# Ethernet1_MDIO.net
KiCad netlist of a schematic drawn in Altium Designer
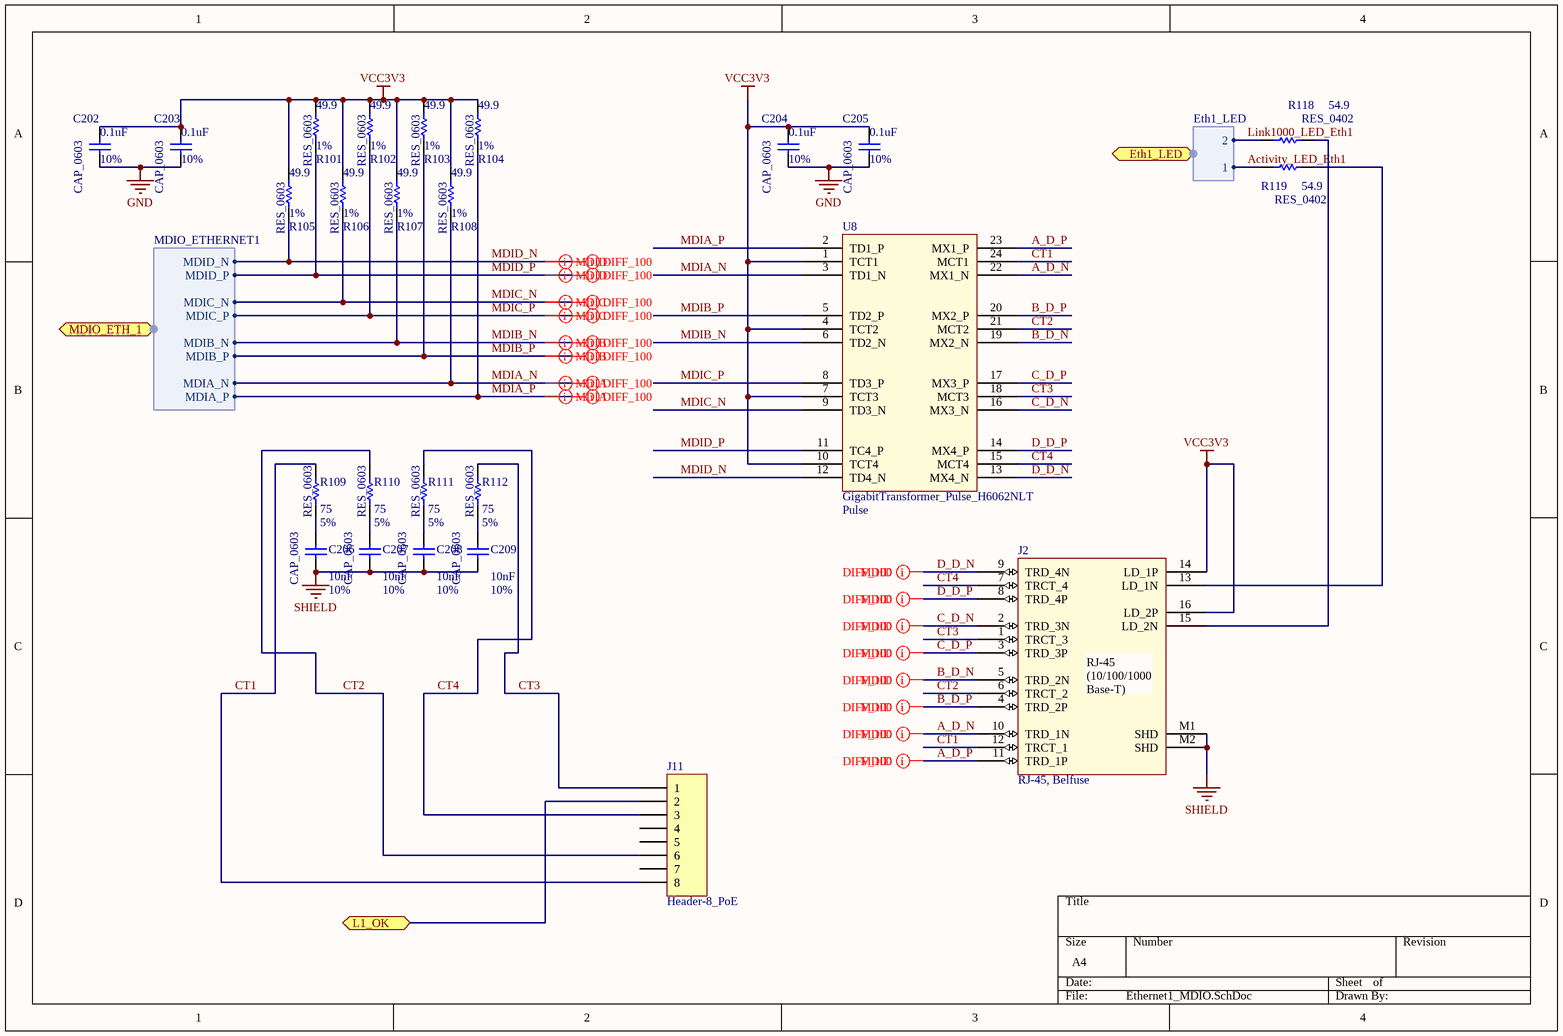
[diagram p0: Ethernet1_MDIO.SchDoc]

(export (version "E")
  (design (tool "Eeschema 10.0.6"))
  (components
    (comp (ref "C202")
      (value "CAP_0603")
      (footprint "CAPC0603(1608)100_N:CAPC0603(1608)100_N")
      (description "CAP CER 0.1UF 50V 10% X7R 0603")
      (fields
        (field (name "ALTIUM_VALUE") "0.1uF")
        (field (name "TOLERANCE") "10%")
        (field (name "PART NUMBER") "C0603C104K5RACTU")
        (field (name "MANUFACTURER") "Kemet")
      )
      (libsource (lib "COMRAD_Database") (part "CAP_0603"))
    )
    (comp (ref "C203")
      (value "CAP_0603")
      (footprint "CAPC0603(1608)100_N:CAPC0603(1608)100_N")
      (description "CAP CER 0.1UF 50V 10% X7R 0603")
      (fields
        (field (name "ALTIUM_VALUE") "0.1uF")
        (field (name "TOLERANCE") "10%")
        (field (name "PART NUMBER") "C0603C104K5RACTU")
        (field (name "MANUFACTURER") "Kemet")
      )
      (libsource (lib "COMRAD_Database") (part "CAP_0603"))
    )
    (comp (ref "C204")
      (value "CAP_0603")
      (footprint "CAPC0603(1608)100_N:CAPC0603(1608)100_N")
      (description "CAP CER 0.1UF 50V 10% X7R 0603")
      (fields
        (field (name "ALTIUM_VALUE") "0.1uF")
        (field (name "TOLERANCE") "10%")
        (field (name "PART NUMBER") "C0603C104K5RACTU")
        (field (name "MANUFACTURER") "Kemet")
      )
      (libsource (lib "COMRAD_Database") (part "CAP_0603"))
    )
    (comp (ref "C205")
      (value "CAP_0603")
      (footprint "CAPC0603(1608)100_N:CAPC0603(1608)100_N")
      (description "CAP CER 0.1UF 50V 10% X7R 0603")
      (fields
        (field (name "ALTIUM_VALUE") "0.1uF")
        (field (name "TOLERANCE") "10%")
        (field (name "PART NUMBER") "C0603C104K5RACTU")
        (field (name "MANUFACTURER") "Kemet")
      )
      (libsource (lib "COMRAD_Database") (part "CAP_0603"))
    )
    (comp (ref "C206")
      (value "CAP_0603")
      (footprint "CAPC0603(1608)100_N:CAPC0603(1608)100_N")
      (description "CAP CER 10000PF 50V 10% X7R 0603")
      (fields
        (field (name "ALTIUM_VALUE") "10nF")
        (field (name "TOLERANCE") "10%")
        (field (name "PART NUMBER") "C0603C103K5RACTU")
        (field (name "MANUFACTURER") "Kemet")
      )
      (libsource (lib "COMRAD_Database") (part "CAP_0603"))
    )
    (comp (ref "C207")
      (value "CAP_0603")
      (footprint "CAPC0603(1608)100_N:CAPC0603(1608)100_N")
      (description "CAP CER 10000PF 50V 10% X7R 0603")
      (fields
        (field (name "ALTIUM_VALUE") "10nF")
        (field (name "TOLERANCE") "10%")
        (field (name "PART NUMBER") "C0603C103K5RACTU")
        (field (name "MANUFACTURER") "Kemet")
      )
      (libsource (lib "COMRAD_Database") (part "CAP_0603"))
    )
    (comp (ref "C208")
      (value "CAP_0603")
      (footprint "CAPC0603(1608)100_N:CAPC0603(1608)100_N")
      (description "CAP CER 10000PF 50V 10% X7R 0603")
      (fields
        (field (name "ALTIUM_VALUE") "10nF")
        (field (name "TOLERANCE") "10%")
        (field (name "PART NUMBER") "C0603C103K5RACTU")
        (field (name "MANUFACTURER") "Kemet")
      )
      (libsource (lib "COMRAD_Database") (part "CAP_0603"))
    )
    (comp (ref "C209")
      (value "CAP_0603")
      (footprint "CAPC0603(1608)100_N:CAPC0603(1608)100_N")
      (description "CAP CER 10000PF 50V 10% X7R 0603")
      (fields
        (field (name "ALTIUM_VALUE") "10nF")
        (field (name "TOLERANCE") "10%")
        (field (name "PART NUMBER") "C0603C103K5RACTU")
        (field (name "MANUFACTURER") "Kemet")
      )
      (libsource (lib "COMRAD_Database") (part "CAP_0603"))
    )
    (comp (ref "J2")
      (value "RJ-45, Belfuse")
      (footprint "RJ-45_BelFuse_L834-1G1T-S7_pcb")
      (description "RJ-45, Belfuse, Gigabit Magnetic Jack")
      (fields (field (name "PART NUMBER") "L834-1G1T-S7") (field (name "MANUFACTURER") "Belfuse"))
      (libsource (lib "COMRAD_Database") (part "RJ-45_BelFuse_L8341GITS7"))
    )
    (comp (ref "J11")
      (value "Header-8_PoE")
      (footprint "Header_FCI_20021221-00008T4LF_8-pos")
      (description "CONN HEADER 8POS DUAL SHRD SMD")
      (fields (field (name "PART NUMBER") "20021221-00008T4LF") (field (name "MANUFACTURER") "FCI"))
      (libsource (lib "COMRAD_Database") (part "Header-8_PoE"))
    )
    (comp (ref "R101")
      (value "RES_0603")
      (footprint "RESC0603(1608)_N")
      (description "RES 49.9 OHM 1/10W 1% 0603 SMD")
      (fields
        (field (name "ALTIUM_VALUE") "49.9")
        (field (name "TOLERANCE") "1%")
        (field (name "PART NUMBER") "ERJ-3EKF49R9V")
        (field (name "MANUFACTURER") "Panasonic Electronics Components")
      )
      (libsource (lib "COMRAD_Database") (part "RES_0603"))
    )
    (comp (ref "R102")
      (value "RES_0603")
      (footprint "RESC0603(1608)_N")
      (description "RES 49.9 OHM 1/10W 1% 0603 SMD")
      (fields
        (field (name "ALTIUM_VALUE") "49.9")
        (field (name "TOLERANCE") "1%")
        (field (name "PART NUMBER") "ERJ-3EKF49R9V")
        (field (name "MANUFACTURER") "Panasonic Electronics Components")
      )
      (libsource (lib "COMRAD_Database") (part "RES_0603"))
    )
    (comp (ref "R103")
      (value "RES_0603")
      (footprint "RESC0603(1608)_N")
      (description "RES 49.9 OHM 1/10W 1% 0603 SMD")
      (fields
        (field (name "ALTIUM_VALUE") "49.9")
        (field (name "TOLERANCE") "1%")
        (field (name "PART NUMBER") "ERJ-3EKF49R9V")
        (field (name "MANUFACTURER") "Panasonic Electronics Components")
      )
      (libsource (lib "COMRAD_Database") (part "RES_0603"))
    )
    (comp (ref "R104")
      (value "RES_0603")
      (footprint "RESC0603(1608)_N")
      (description "RES 49.9 OHM 1/10W 1% 0603 SMD")
      (fields
        (field (name "ALTIUM_VALUE") "49.9")
        (field (name "TOLERANCE") "1%")
        (field (name "PART NUMBER") "ERJ-3EKF49R9V")
        (field (name "MANUFACTURER") "Panasonic Electronics Components")
      )
      (libsource (lib "COMRAD_Database") (part "RES_0603"))
    )
    (comp (ref "R105")
      (value "RES_0603")
      (footprint "RESC0603(1608)_N")
      (description "RES 49.9 OHM 1/10W 1% 0603 SMD")
      (fields
        (field (name "ALTIUM_VALUE") "49.9")
        (field (name "TOLERANCE") "1%")
        (field (name "PART NUMBER") "ERJ-3EKF49R9V")
        (field (name "MANUFACTURER") "Panasonic Electronics Components")
      )
      (libsource (lib "COMRAD_Database") (part "RES_0603"))
    )
    (comp (ref "R106")
      (value "RES_0603")
      (footprint "RESC0603(1608)_N")
      (description "RES 49.9 OHM 1/10W 1% 0603 SMD")
      (fields
        (field (name "ALTIUM_VALUE") "49.9")
        (field (name "TOLERANCE") "1%")
        (field (name "PART NUMBER") "ERJ-3EKF49R9V")
        (field (name "MANUFACTURER") "Panasonic Electronics Components")
      )
      (libsource (lib "COMRAD_Database") (part "RES_0603"))
    )
    (comp (ref "R107")
      (value "RES_0603")
      (footprint "RESC0603(1608)_N")
      (description "RES 49.9 OHM 1/10W 1% 0603 SMD")
      (fields
        (field (name "ALTIUM_VALUE") "49.9")
        (field (name "TOLERANCE") "1%")
        (field (name "PART NUMBER") "ERJ-3EKF49R9V")
        (field (name "MANUFACTURER") "Panasonic Electronics Components")
      )
      (libsource (lib "COMRAD_Database") (part "RES_0603"))
    )
    (comp (ref "R108")
      (value "RES_0603")
      (footprint "RESC0603(1608)_N")
      (description "RES 49.9 OHM 1/10W 1% 0603 SMD")
      (fields
        (field (name "ALTIUM_VALUE") "49.9")
        (field (name "TOLERANCE") "1%")
        (field (name "PART NUMBER") "ERJ-3EKF49R9V")
        (field (name "MANUFACTURER") "Panasonic Electronics Components")
      )
      (libsource (lib "COMRAD_Database") (part "RES_0603"))
    )
    (comp (ref "R109")
      (value "RES_0603")
      (footprint "RESC0603(1608)_N")
      (description "RES 75 OHM 1/10W 5% 0603 SMD")
      (fields
        (field (name "ALTIUM_VALUE") "75")
        (field (name "TOLERANCE") "5%")
        (field (name "PART NUMBER") "ERJ-3GEYJ750V")
        (field (name "MANUFACTURER") "Panasonic Electronic Components")
      )
      (libsource (lib "COMRAD_Database") (part "RES_0603"))
    )
    (comp (ref "R110")
      (value "RES_0603")
      (footprint "RESC0603(1608)_N")
      (description "RES 75 OHM 1/10W 5% 0603 SMD")
      (fields
        (field (name "ALTIUM_VALUE") "75")
        (field (name "TOLERANCE") "5%")
        (field (name "PART NUMBER") "ERJ-3GEYJ750V")
        (field (name "MANUFACTURER") "Panasonic Electronic Components")
      )
      (libsource (lib "COMRAD_Database") (part "RES_0603"))
    )
    (comp (ref "R111")
      (value "RES_0603")
      (footprint "RESC0603(1608)_N")
      (description "RES 75 OHM 1/10W 5% 0603 SMD")
      (fields
        (field (name "ALTIUM_VALUE") "75")
        (field (name "TOLERANCE") "5%")
        (field (name "PART NUMBER") "ERJ-3GEYJ750V")
        (field (name "MANUFACTURER") "Panasonic Electronic Components")
      )
      (libsource (lib "COMRAD_Database") (part "RES_0603"))
    )
    (comp (ref "R112")
      (value "RES_0603")
      (footprint "RESC0603(1608)_N")
      (description "RES 75 OHM 1/10W 5% 0603 SMD")
      (fields
        (field (name "ALTIUM_VALUE") "75")
        (field (name "TOLERANCE") "5%")
        (field (name "PART NUMBER") "ERJ-3GEYJ750V")
        (field (name "MANUFACTURER") "Panasonic Electronic Components")
      )
      (libsource (lib "COMRAD_Database") (part "RES_0603"))
    )
    (comp (ref "R118")
      (value "RES_0402")
      (footprint "RESC0402(1005)_N")
      (description "RES 54.9 OHM 1/10W 1% 0402 SMD")
      (fields
        (field (name "ALTIUM_VALUE") "54.9")
        (field (name "PART NUMBER") "ERJ-2RKF54R9X")
        (field (name "MANUFACTURER") "Panasonic Electronic Components")
      )
      (libsource (lib "COMRAD_Database") (part "RES_0402"))
    )
    (comp (ref "R119")
      (value "RES_0402")
      (footprint "RESC0402(1005)_N")
      (description "RES 54.9 OHM 1/10W 1% 0402 SMD")
      (fields
        (field (name "ALTIUM_VALUE") "54.9")
        (field (name "PART NUMBER") "ERJ-2RKF54R9X")
        (field (name "MANUFACTURER") "Panasonic Electronic Components")
      )
      (libsource (lib "COMRAD_Database") (part "RES_0402"))
    )
    (comp (ref "U8")
      (value "GigabitTransformer_Pulse_H6062NLT")
      (footprint "GigabitTransformer_H6062NLT_SOP-24")
      (description "Magnetics, GigabitTransformer, H6062NLT, Pulse")
      (fields (field (name "PART NUMBER") "H6062NLT") (field (name "MANUFACTURER") "Pulse"))
      (libsource (lib "COMRAD_Database") (part "GigabitTransformer_H6062NLT"))
    )
  )
  (nets
    (net (code "3") (name "/A_D_N") (class "Default")
      (node (ref "J2") (pin "10") (pinfunction "TRD_1N_10") (pintype "bidirectional"))
      (node (ref "U8") (pin "22") (pinfunction "MX1_N_22") (pintype "passive"))
    )
    (net (code "4") (name "/A_D_P") (class "Default")
      (node (ref "J2") (pin "11") (pinfunction "TRD_1P_11") (pintype "bidirectional"))
      (node (ref "U8") (pin "23") (pinfunction "MX1_P_23") (pintype "passive"))
    )
    (net (code "5") (name "/Activity_LED_Eth1") (class "Default")
      (node (ref "R119") (pin "2") (pinfunction "2_2") (pintype "passive"))
    )
    (net (code "6") (name "/B_D_N") (class "Default")
      (node (ref "J2") (pin "5") (pinfunction "TRD_2N_5") (pintype "bidirectional"))
      (node (ref "U8") (pin "19") (pinfunction "MX2_N_19") (pintype "passive"))
    )
    (net (code "7") (name "/B_D_P") (class "Default")
      (node (ref "J2") (pin "4") (pinfunction "TRD_2P_4") (pintype "bidirectional"))
      (node (ref "U8") (pin "20") (pinfunction "MX2_P_20") (pintype "passive"))
    )
    (net (code "8") (name "/CT1") (class "Default")
      (node (ref "J11") (pin "8") (pinfunction "8_8") (pintype "passive"))
      (node (ref "J2") (pin "12") (pinfunction "TRCT_1_12") (pintype "bidirectional"))
      (node (ref "R109") (pin "2") (pinfunction "2_2") (pintype "passive"))
      (node (ref "U8") (pin "24") (pinfunction "MCT1_24") (pintype "passive"))
    )
    (net (code "9") (name "/CT2") (class "Default")
      (node (ref "J11") (pin "6") (pinfunction "6_6") (pintype "passive"))
      (node (ref "J2") (pin "6") (pinfunction "TRCT_2_6") (pintype "bidirectional"))
      (node (ref "R110") (pin "2") (pinfunction "2_2") (pintype "passive"))
      (node (ref "U8") (pin "21") (pinfunction "MCT2_21") (pintype "passive"))
    )
    (net (code "10") (name "/CT3") (class "Default")
      (node (ref "J11") (pin "1") (pinfunction "1_1") (pintype "passive"))
      (node (ref "J2") (pin "1") (pinfunction "TRCT_3_1") (pintype "bidirectional"))
      (node (ref "R112") (pin "2") (pinfunction "2_2") (pintype "passive"))
      (node (ref "U8") (pin "18") (pinfunction "MCT3_18") (pintype "passive"))
    )
    (net (code "11") (name "/CT4") (class "Default")
      (node (ref "J11") (pin "3") (pinfunction "3_3") (pintype "passive"))
      (node (ref "J2") (pin "7") (pinfunction "TRCT_4_7") (pintype "bidirectional"))
      (node (ref "R111") (pin "2") (pinfunction "2_2") (pintype "passive"))
      (node (ref "U8") (pin "15") (pinfunction "MCT4_15") (pintype "passive"))
    )
    (net (code "12") (name "/C_D_N") (class "Default")
      (node (ref "J2") (pin "2") (pinfunction "TRD_3N_2") (pintype "bidirectional"))
      (node (ref "U8") (pin "16") (pinfunction "MX3_N_16") (pintype "passive"))
    )
    (net (code "13") (name "/C_D_P") (class "Default")
      (node (ref "J2") (pin "3") (pinfunction "TRD_3P_3") (pintype "bidirectional"))
      (node (ref "U8") (pin "17") (pinfunction "MX3_P_17") (pintype "passive"))
    )
    (net (code "14") (name "/D_D_N") (class "Default")
      (node (ref "J2") (pin "9") (pinfunction "TRD_4N_9") (pintype "bidirectional"))
      (node (ref "U8") (pin "13") (pinfunction "MX4_N_13") (pintype "passive"))
    )
    (net (code "15") (name "/D_D_P") (class "Default")
      (node (ref "J2") (pin "8") (pinfunction "TRD_4P_8") (pintype "bidirectional"))
      (node (ref "U8") (pin "14") (pinfunction "MX4_P_14") (pintype "passive"))
    )
    (net (code "16") (name "/L1_OK") (class "Default")
      (node (ref "J11") (pin "2") (pinfunction "2_2") (pintype "passive"))
    )
    (net (code "17") (name "/Link1000_LED_Eth1") (class "Default")
      (node (ref "R118") (pin "2") (pinfunction "2_2") (pintype "passive"))
    )
    (net (code "18") (name "/MDIA_N") (class "Default")
      (node (ref "R108") (pin "1") (pinfunction "1_1") (pintype "passive"))
      (node (ref "U8") (pin "3") (pinfunction "TD1_N_3") (pintype "passive"))
    )
    (net (code "19") (name "/MDIA_P") (class "Default")
      (node (ref "R104") (pin "1") (pinfunction "1_1") (pintype "passive"))
      (node (ref "U8") (pin "2") (pinfunction "TD1_P_2") (pintype "passive"))
    )
    (net (code "20") (name "/MDIB_N") (class "Default")
      (node (ref "R107") (pin "1") (pinfunction "1_1") (pintype "passive"))
      (node (ref "U8") (pin "6") (pinfunction "TD2_N_6") (pintype "passive"))
    )
    (net (code "21") (name "/MDIB_P") (class "Default")
      (node (ref "R103") (pin "1") (pinfunction "1_1") (pintype "passive"))
      (node (ref "U8") (pin "5") (pinfunction "TD2_P_5") (pintype "passive"))
    )
    (net (code "22") (name "/MDIC_N") (class "Default")
      (node (ref "R106") (pin "1") (pinfunction "1_1") (pintype "passive"))
      (node (ref "U8") (pin "9") (pinfunction "TD3_N_9") (pintype "passive"))
    )
    (net (code "23") (name "/MDIC_P") (class "Default")
      (node (ref "R102") (pin "1") (pinfunction "1_1") (pintype "passive"))
      (node (ref "U8") (pin "8") (pinfunction "TD3_P_8") (pintype "passive"))
    )
    (net (code "24") (name "/MDID_N") (class "Default")
      (node (ref "R105") (pin "1") (pinfunction "1_1") (pintype "passive"))
      (node (ref "U8") (pin "12") (pinfunction "TD4_N_12") (pintype "passive"))
    )
    (net (code "25") (name "/MDID_P") (class "Default")
      (node (ref "R101") (pin "1") (pinfunction "1_1") (pintype "passive"))
      (node (ref "U8") (pin "11") (pinfunction "TC4_P_11") (pintype "passive"))
    )
    (net (code "28") (name "GND") (class "Default")
      (node (ref "C202") (pin "1") (pinfunction "1_1") (pintype "passive"))
      (node (ref "C203") (pin "1") (pinfunction "1_1") (pintype "passive"))
      (node (ref "C204") (pin "1") (pinfunction "1_1") (pintype "passive"))
      (node (ref "C205") (pin "1") (pinfunction "1_1") (pintype "passive"))
    )
    (net (code "29") (name "Net-(C206-Pad2)") (class "Default")
      (node (ref "C206") (pin "2") (pinfunction "2_2") (pintype "passive"))
      (node (ref "R109") (pin "1") (pinfunction "1_1") (pintype "passive"))
    )
    (net (code "30") (name "Net-(C207-Pad2)") (class "Default")
      (node (ref "C207") (pin "2") (pinfunction "2_2") (pintype "passive"))
      (node (ref "R110") (pin "1") (pinfunction "1_1") (pintype "passive"))
    )
    (net (code "31") (name "Net-(C208-Pad2)") (class "Default")
      (node (ref "C208") (pin "2") (pinfunction "2_2") (pintype "passive"))
      (node (ref "R111") (pin "1") (pinfunction "1_1") (pintype "passive"))
    )
    (net (code "32") (name "Net-(C209-Pad2)") (class "Default")
      (node (ref "C209") (pin "2") (pinfunction "2_2") (pintype "passive"))
      (node (ref "R112") (pin "1") (pinfunction "1_1") (pintype "passive"))
    )
    (net (code "33") (name "Net-(J2-LD_1N)") (class "Default")
      (node (ref "J2") (pin "13") (pinfunction "LD_1N_13") (pintype "passive"))
      (node (ref "R119") (pin "1") (pinfunction "1_1") (pintype "passive"))
    )
    (net (code "34") (name "Net-(J2-LD_2N)") (class "Default")
      (node (ref "J2") (pin "15") (pinfunction "LD_2N_15") (pintype "passive"))
      (node (ref "R118") (pin "1") (pinfunction "1_1") (pintype "passive"))
    )
    (net (code "35") (name "SHIELD") (class "Default")
      (node (ref "C206") (pin "1") (pinfunction "1_1") (pintype "passive"))
      (node (ref "C207") (pin "1") (pinfunction "1_1") (pintype "passive"))
      (node (ref "C208") (pin "1") (pinfunction "1_1") (pintype "passive"))
      (node (ref "C209") (pin "1") (pinfunction "1_1") (pintype "passive"))
      (node (ref "J2") (pin "M1") (pinfunction "SHD_M1") (pintype "power_in"))
      (node (ref "J2") (pin "M2") (pinfunction "SHD_M2") (pintype "power_in"))
    )
    (net (code "36") (name "VCC3V3") (class "Default")
      (node (ref "C202") (pin "2") (pinfunction "2_2") (pintype "passive"))
      (node (ref "C203") (pin "2") (pinfunction "2_2") (pintype "passive"))
      (node (ref "C204") (pin "2") (pinfunction "2_2") (pintype "passive"))
      (node (ref "C205") (pin "2") (pinfunction "2_2") (pintype "passive"))
      (node (ref "J2") (pin "14") (pinfunction "LD_1P_14") (pintype "passive"))
      (node (ref "J2") (pin "16") (pinfunction "LD_2P_16") (pintype "passive"))
      (node (ref "R101") (pin "2") (pinfunction "2_2") (pintype "passive"))
      (node (ref "R102") (pin "2") (pinfunction "2_2") (pintype "passive"))
      (node (ref "R103") (pin "2") (pinfunction "2_2") (pintype "passive"))
      (node (ref "R104") (pin "2") (pinfunction "2_2") (pintype "passive"))
      (node (ref "R105") (pin "2") (pinfunction "2_2") (pintype "passive"))
      (node (ref "R106") (pin "2") (pinfunction "2_2") (pintype "passive"))
      (node (ref "R107") (pin "2") (pinfunction "2_2") (pintype "passive"))
      (node (ref "R108") (pin "2") (pinfunction "2_2") (pintype "passive"))
      (node (ref "U8") (pin "1") (pinfunction "TCT1_1") (pintype "passive"))
      (node (ref "U8") (pin "10") (pinfunction "TCT4_10") (pintype "passive"))
      (node (ref "U8") (pin "4") (pinfunction "TCT2_4") (pintype "passive"))
      (node (ref "U8") (pin "7") (pinfunction "TCT3_7") (pintype "passive"))
    )
    (net (code "37") (name "unconnected-(J11-Pad4)") (class "Default")
      (node (ref "J11") (pin "4") (pinfunction "4_4") (pintype "passive"))
    )
    (net (code "38") (name "unconnected-(J11-Pad5)") (class "Default")
      (node (ref "J11") (pin "5") (pinfunction "5_5") (pintype "passive"))
    )
    (net (code "39") (name "unconnected-(J11-Pad7)") (class "Default")
      (node (ref "J11") (pin "7") (pinfunction "7_7") (pintype "passive"))
    )
  )
)
